# EtherWiz_Controller.net
KiCad netlist of a schematic drawn in Altium Designer
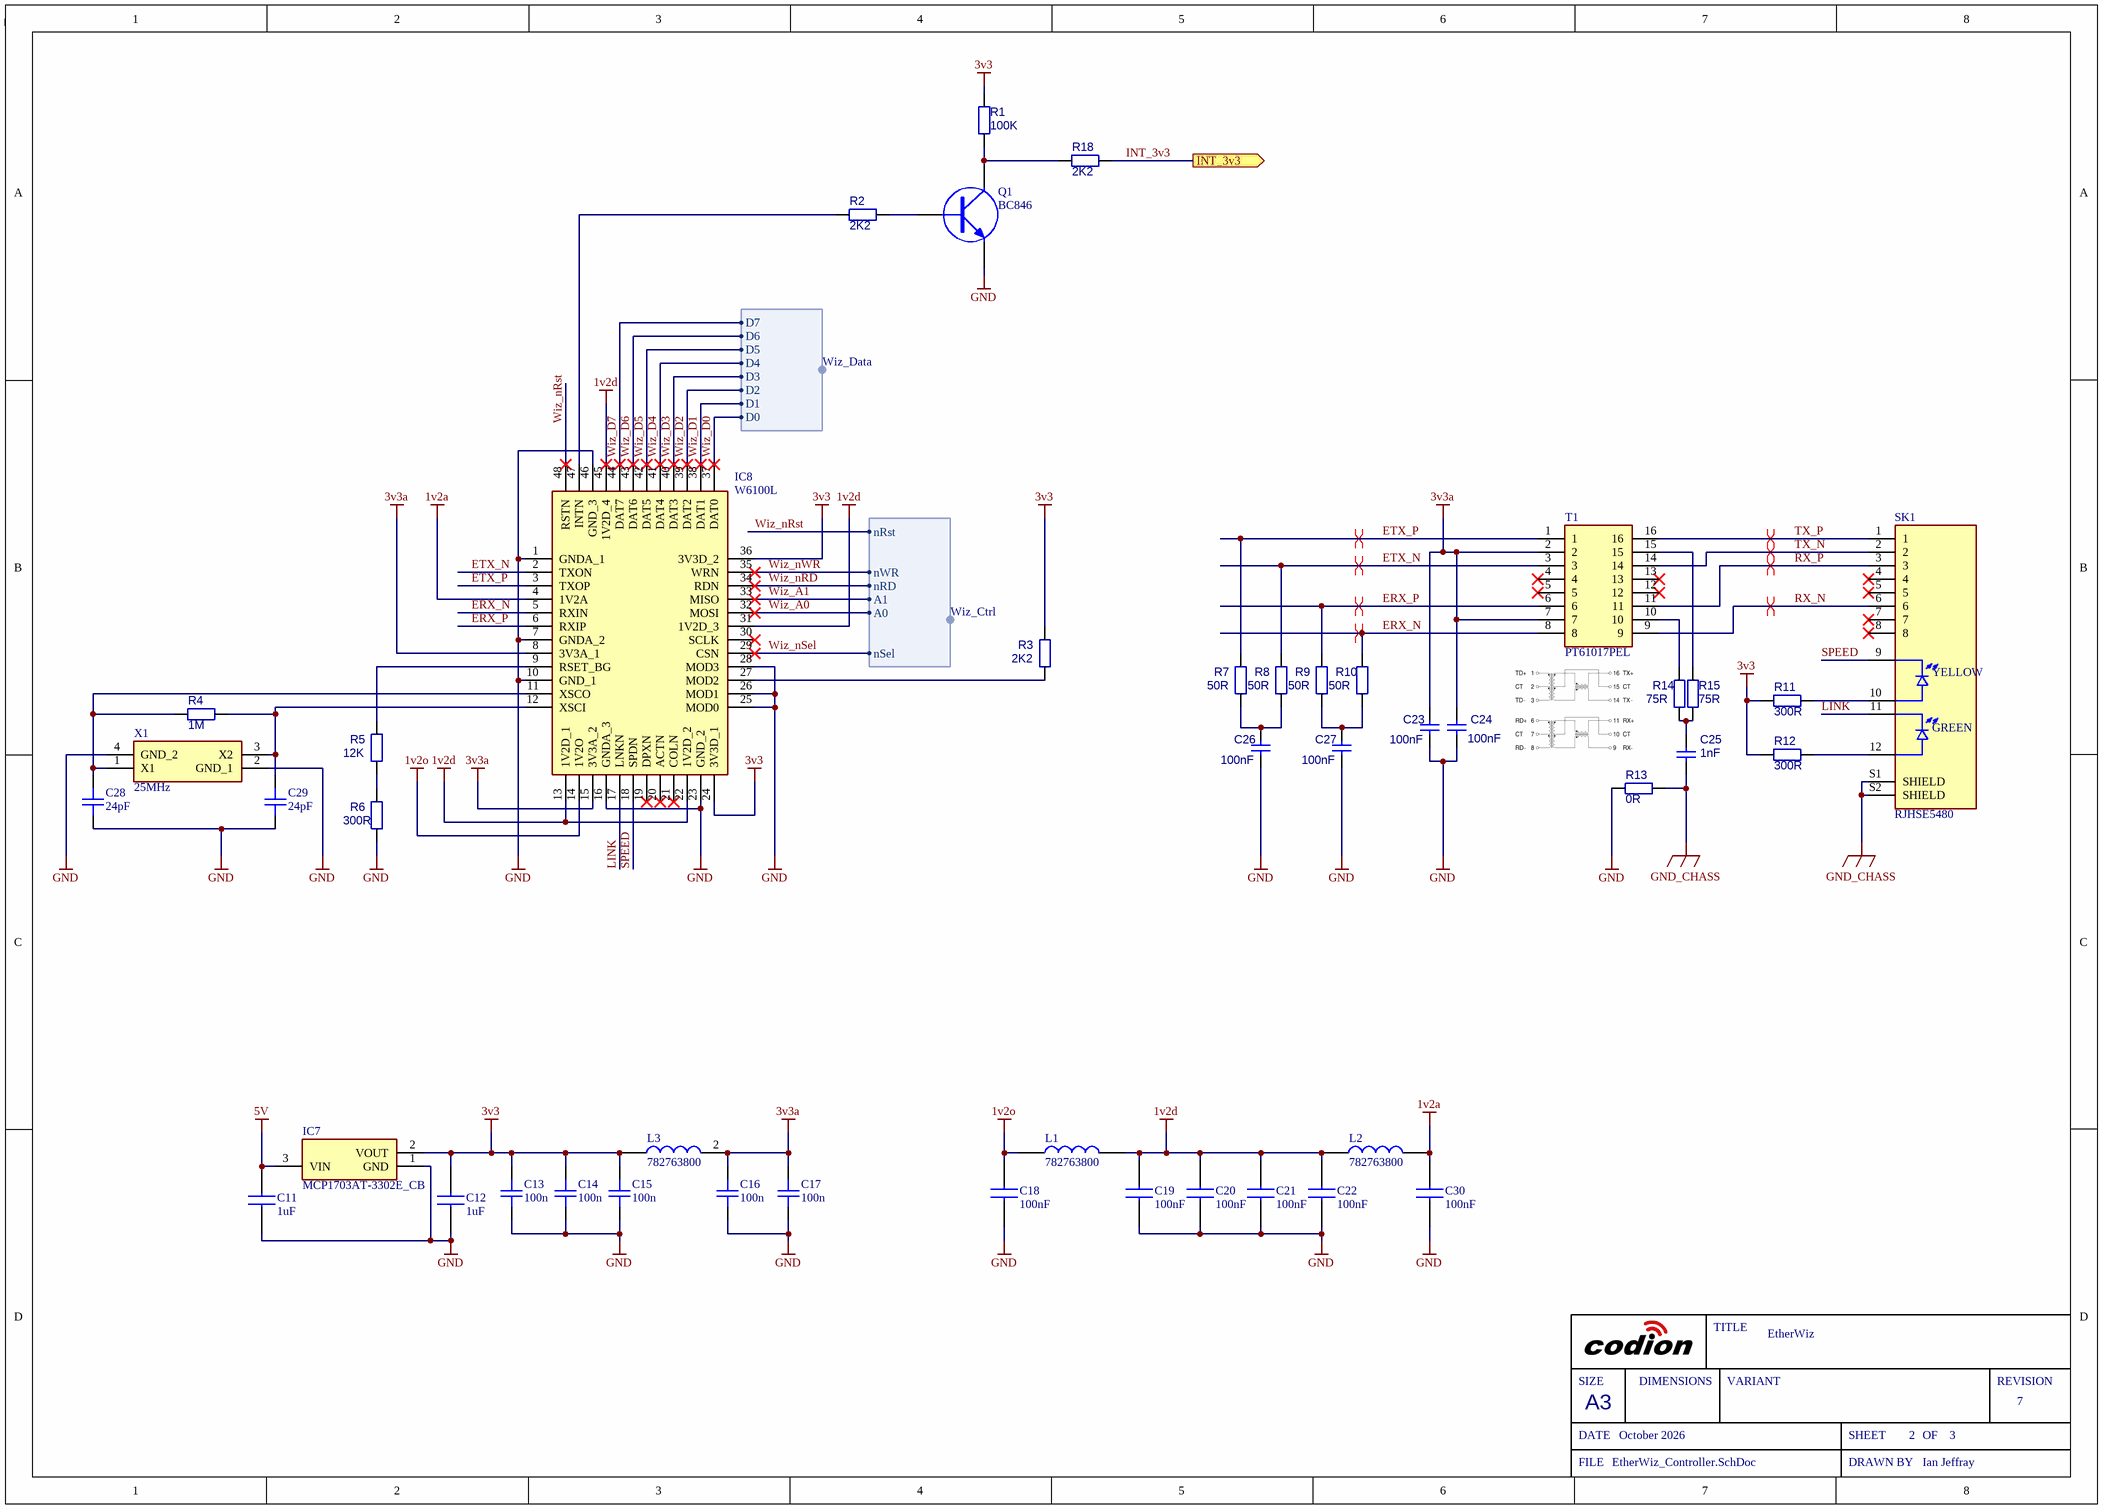
[diagram p0: EtherWiz_Controller.SchDoc]

(export (version "E")
  (design (tool "Eeschema 10.0.6"))
  (components
    (comp (ref "C11")
      (value "1uF")
      (footprint "SamacSys:CAPC1608X90N")
      (description "Capacitor")
      (fields
        (field (name "MANUFACTURER_PART_NUMBER") "CL10A105KP8NNNC")
        (field (name "MOUSER PART NUMBER") "187-CL10A105KP8NNNC")
      )
      (libsource (lib "*") (part "CL10A105KP8NNNC"))
    )
    (comp (ref "C12")
      (value "1uF")
      (footprint "SamacSys:CAPC1608X90N")
      (description "Capacitor")
      (fields
        (field (name "MANUFACTURER_PART_NUMBER") "CL10A105KP8NNNC")
        (field (name "MOUSER PART NUMBER") "187-CL10A105KP8NNNC")
      )
      (libsource (lib "*") (part "CL10A105KP8NNNC"))
    )
    (comp (ref "C13")
      (value "100n")
      (footprint "CAPC1608L")
      (description "CAP 100nF, 0603, 50V, X7R, 10%")
      (fields
        (field (name "DISTRIBUTOR1 PART NO") "CL10B104KB8NNNC")
        (field (name "DISTRIBUTOR2 PART NO") "311-1344-2-ND")
      )
      (libsource (lib "MCP1002_RevC") (part "CAP_100n_0603_50V_0"))
    )
    (comp (ref "C14")
      (value "100n")
      (footprint "CAPC1608L")
      (description "CAP 100nF, 0603, 50V, X7R, 10%")
      (fields
        (field (name "DISTRIBUTOR1 PART NO") "CL10B104KB8NNNC")
        (field (name "DISTRIBUTOR2 PART NO") "311-1344-2-ND")
      )
      (libsource (lib "MCP1002_RevC") (part "CAP_100n_0603_50V_0"))
    )
    (comp (ref "C15")
      (value "100n")
      (footprint "CAPC1608L")
      (description "CAP 100nF, 0603, 50V, X7R, 10%")
      (fields
        (field (name "DISTRIBUTOR1 PART NO") "CL10B104KB8NNNC")
        (field (name "DISTRIBUTOR2 PART NO") "311-1344-2-ND")
      )
      (libsource (lib "MCP1002_RevC") (part "CAP_100n_0603_50V_0"))
    )
    (comp (ref "C16")
      (value "100n")
      (footprint "CAPC1608L")
      (description "CAP 100nF, 0603, 50V, X7R, 10%")
      (fields
        (field (name "DISTRIBUTOR1 PART NO") "CL10B104KB8NNNC")
        (field (name "DISTRIBUTOR2 PART NO") "311-1344-2-ND")
      )
      (libsource (lib "MCP1002_RevC") (part "CAP_100n_0603_50V_0"))
    )
    (comp (ref "C17")
      (value "100n")
      (footprint "CAPC1608L")
      (description "CAP 100nF, 0603, 50V, X7R, 10%")
      (fields
        (field (name "DISTRIBUTOR1 PART NO") "CL10B104KB8NNNC")
        (field (name "DISTRIBUTOR2 PART NO") "311-1344-2-ND")
      )
      (libsource (lib "MCP1002_RevC") (part "CAP_100n_0603_50V_0"))
    )
    (comp (ref "C18")
      (value "100nF")
      (footprint "CAPC1608L")
      (description "Capacitor")
      (fields
        (field (name "MANUFACTURER_PART_NUMBER") "C2012X7R1H104K125AM")
        (field (name "MOUSER PART NUMBER") "810-C2012X7R1H104KT5")
      )
      (libsource (lib "Acorn") (part "100nF0805"))
    )
    (comp (ref "C19")
      (value "100nF")
      (footprint "CAPC1608L")
      (description "Capacitor")
      (fields
        (field (name "MANUFACTURER_PART_NUMBER") "C2012X7R1H104K125AM")
        (field (name "MOUSER PART NUMBER") "810-C2012X7R1H104KT5")
      )
      (libsource (lib "Acorn") (part "100nF0805"))
    )
    (comp (ref "C20")
      (value "100nF")
      (footprint "CAPC1608L")
      (description "Capacitor")
      (fields
        (field (name "MANUFACTURER_PART_NUMBER") "C2012X7R1H104K125AM")
        (field (name "MOUSER PART NUMBER") "810-C2012X7R1H104KT5")
      )
      (libsource (lib "Acorn") (part "100nF0805"))
    )
    (comp (ref "C21")
      (value "100nF")
      (footprint "CAPC1608L")
      (description "Capacitor")
      (fields
        (field (name "MANUFACTURER_PART_NUMBER") "C2012X7R1H104K125AM")
        (field (name "MOUSER PART NUMBER") "810-C2012X7R1H104KT5")
      )
      (libsource (lib "Acorn") (part "100nF0805"))
    )
    (comp (ref "C22")
      (value "100nF")
      (footprint "CAPC1608L")
      (description "Capacitor")
      (fields
        (field (name "MANUFACTURER_PART_NUMBER") "C2012X7R1H104K125AM")
        (field (name "MOUSER PART NUMBER") "810-C2012X7R1H104KT5")
      )
      (libsource (lib "Acorn") (part "100nF0805"))
    )
    (comp (ref "C23")
      (value "100nF")
      (footprint "CAPC1608L")
      (description "Cap ceramic X7R/X5R 100nF 10% 16V C0603")
      (fields (field (name "TOLERANCE") "0.1") (field (name "VOLTAGE") "16V"))
      (libsource (lib "Local_Altium_Lib") (part "Capacitor - non polarized"))
    )
    (comp (ref "C24")
      (value "100nF")
      (footprint "CAPC1608L")
      (description "Cap ceramic X7R/X5R 100nF 10% 16V C0603")
      (fields (field (name "TOLERANCE") "0.1") (field (name "VOLTAGE") "16V"))
      (libsource (lib "Local_Altium_Lib") (part "Capacitor - non polarized"))
    )
    (comp (ref "C25")
      (value "1nF")
      (footprint "CAPC1608L")
      (description "Cap ceramic X7R 1nF 10% 2kV C1206")
      (fields (field (name "TOLERANCE") "0.1") (field (name "VOLTAGE") "2000V"))
      (libsource (lib "Local_Altium_Lib") (part "Capacitor - non polarized"))
    )
    (comp (ref "C26")
      (value "100nF")
      (footprint "CAPC1608L")
      (description "Cap ceramic X7R/X5R 100nF 10% 16V C0603")
      (fields (field (name "TOLERANCE") "0.1") (field (name "VOLTAGE") "16V"))
      (libsource (lib "Local_Altium_Lib") (part "Capacitor - non polarized"))
    )
    (comp (ref "C27")
      (value "100nF")
      (footprint "CAPC1608L")
      (description "Cap ceramic X7R/X5R 100nF 10% 16V C0603")
      (fields (field (name "TOLERANCE") "0.1") (field (name "VOLTAGE") "16V"))
      (libsource (lib "Local_Altium_Lib") (part "Capacitor - non polarized"))
    )
    (comp (ref "C28")
      (value "24pF")
      (footprint "CAPC1608L")
      (description "CAP 10PF, 0603, 50V, NP0, 10%")
      (libsource (lib "MCP1010_RevA") (part "CAP_10P_0603_50V_0"))
    )
    (comp (ref "C29")
      (value "24pF")
      (footprint "CAPC1608L")
      (description "CAP 10PF, 0603, 50V, NP0, 10%")
      (libsource (lib "MCP1010_RevA") (part "CAP_10P_0603_50V_0"))
    )
    (comp (ref "C30")
      (value "100nF")
      (footprint "CAPC1608L")
      (description "Capacitor")
      (fields
        (field (name "MANUFACTURER_PART_NUMBER") "C2012X7R1H104K125AM")
        (field (name "MOUSER PART NUMBER") "810-C2012X7R1H104KT5")
      )
      (libsource (lib "Acorn") (part "100nF0805"))
    )
    (comp (ref "IC7")
      (value "MCP1703AT-3302E_CB")
      (footprint "SamacSys:SOT95P255X145-3N")
      (description "Integrated Circuit")
      (fields
        (field (name "MANUFACTURER_PART_NUMBER") "MCP1703AT-3302E/CB")
        (field (name "MOUSER PART NUMBER") "579-MCP1703AT3302ECB")
      )
      (libsource (lib "*") (part "MCP1703AT-3302E_CB"))
    )
    (comp (ref "IC8")
      (value "W6100L")
      (footprint "SamacSys:QFP50P900X900X160-48N")
      (description "Integrated Circuit")
      (fields (field (name "MOUSER PART NUMBER") "950-W6100L"))
      (libsource (lib "*") (part "W6100L"))
    )
    (comp (ref "L1")
      (value "782763800")
      (footprint "SamacSys:INDC3216X130N")
      (description "Inductor")
      (fields (field (name "MOUSER PART NUMBER") "710-782763800"))
      (libsource (lib "*") (part "74279215"))
    )
    (comp (ref "L2")
      (value "782763800")
      (footprint "SamacSys:INDC3216X130N")
      (description "Inductor")
      (fields (field (name "MOUSER PART NUMBER") "710-782763800"))
      (libsource (lib "*") (part "74279215"))
    )
    (comp (ref "L3")
      (value "782763800")
      (footprint "SamacSys:INDC3216X130N")
      (description "Inductor")
      (fields (field (name "MOUSER PART NUMBER") "710-782763800"))
      (libsource (lib "") (part "74279215_1"))
    )
    (comp (ref "Q1")
      (value "BC846")
      (footprint "SOT-23")
      (description "Transistor NPN, 65V, 100mA, TO-236AB/SOT23")
      (libsource (lib "MCP1002_RevC") (part "TRANS_NPN_BC846_0"))
    )
    (comp (ref "R1")
      (value "100K")
      (footprint "RESC1608X50N")
      (description "Resistor 100K 1%  0603")
      (libsource (lib "Local_Altium_Lib") (part "Resistor - fixed"))
    )
    (comp (ref "R2")
      (value "2K2")
      (footprint "RESC1608X50N")
      (description "Resistor 2K2 1%  0603")
      (fields (field (name "TOLERANCE") "0.01") (field (name "POWER") "63mW"))
      (libsource (lib "") (part "Resistor - fixed_2"))
    )
    (comp (ref "R3")
      (value "2K2")
      (footprint "RESC1608X50N")
      (description "Resistor 2K2 1%  0603")
      (fields (field (name "TOLERANCE") "0.01") (field (name "POWER") "63mW"))
      (libsource (lib "Local_Altium_Lib") (part "Resistor - fixed"))
    )
    (comp (ref "R4")
      (value "1M")
      (footprint "RESC1608X50N")
      (description "Resistor 1M 1%  0603")
      (fields (field (name "TOLERANCE") "0.01") (field (name "POWER") "63mW"))
      (libsource (lib "") (part "Resistor - fixed_1"))
    )
    (comp (ref "R5")
      (value "12K")
      (footprint "RESC1608X50N")
      (description "Resistor 12K 1%  0603")
      (fields (field (name "TOLERANCE") "0.01") (field (name "POWER") "63mW"))
      (libsource (lib "Local_Altium_Lib") (part "Resistor - fixed"))
    )
    (comp (ref "R6")
      (value "300R")
      (footprint "RESC1608X50N")
      (description "Resistor 300R 1%  0603")
      (fields (field (name "TOLERANCE") "0.01") (field (name "POWER") "63mW"))
      (libsource (lib "Local_Altium_Lib") (part "Resistor - fixed"))
    )
    (comp (ref "R7")
      (value "50R")
      (footprint "RESC1608X50N")
      (description "Resistor 50R 1%  0603")
      (fields (field (name "TOLERANCE") "0.01") (field (name "POWER") "63mW"))
      (libsource (lib "Local_Altium_Lib") (part "Resistor - fixed"))
    )
    (comp (ref "R8")
      (value "50R")
      (footprint "RESC1608X50N")
      (description "Resistor 50R 1%  0603")
      (fields (field (name "TOLERANCE") "0.01") (field (name "POWER") "63mW"))
      (libsource (lib "Local_Altium_Lib") (part "Resistor - fixed"))
    )
    (comp (ref "R9")
      (value "50R")
      (footprint "RESC1608X50N")
      (description "Resistor 50R 1%  0603")
      (fields (field (name "TOLERANCE") "0.01") (field (name "POWER") "63mW"))
      (libsource (lib "Local_Altium_Lib") (part "Resistor - fixed"))
    )
    (comp (ref "R10")
      (value "50R")
      (footprint "RESC1608X50N")
      (description "Resistor 50R 1%  0603")
      (fields (field (name "TOLERANCE") "0.01") (field (name "POWER") "63mW"))
      (libsource (lib "Local_Altium_Lib") (part "Resistor - fixed"))
    )
    (comp (ref "R11")
      (value "300R")
      (footprint "RESC1608X50N")
      (description "Resistor 300R 1%  0603")
      (libsource (lib "") (part "Resistor - fixed_1"))
    )
    (comp (ref "R12")
      (value "300R")
      (footprint "RESC1608X50N")
      (description "Resistor 300R 1%  0603")
      (libsource (lib "") (part "Resistor - fixed_1"))
    )
    (comp (ref "R13")
      (value "0R")
      (footprint "RESC1608L")
      (description "Resistor 0R0 1A Max 0603")
      (fields (field (name "MANUFACTURER") "Vishay") (field (name "MANUPART") "CRCW06030000Z0EA"))
      (libsource (lib "") (part "Resistor - fixed_2"))
    )
    (comp (ref "R14")
      (value "75R")
      (footprint "RESC1608L")
      (description "Resistor 75R 1%  0603")
      (fields (field (name "TOLERANCE") "0.01") (field (name "POWER") "63mW"))
      (libsource (lib "Local_Altium_Lib") (part "Resistor - fixed"))
    )
    (comp (ref "R15")
      (value "75R")
      (footprint "RESC1608L")
      (description "Resistor 75R 1%  0603")
      (fields (field (name "TOLERANCE") "0.01") (field (name "POWER") "63mW"))
      (libsource (lib "Local_Altium_Lib") (part "Resistor - fixed"))
    )
    (comp (ref "R18")
      (value "2K2")
      (footprint "RESC1608X50N")
      (description "Resistor 2K2 1%  0603")
      (fields (field (name "TOLERANCE") "0.01") (field (name "POWER") "63mW"))
      (libsource (lib "") (part "Resistor - fixed_2"))
    )
    (comp (ref "SK1")
      (value "RJHSE5480")
      (footprint "AMPHENOL_RJHSE5480")
      (description "Ethernet socket - through hole")
      (fields (field (name "MANUPART") "RJHSE-5480") (field (name "MANUFACTURER") "Amphenol"))
      (libsource (lib "RJHSE5480") (part "RJHSE5480"))
    )
    (comp (ref "T1")
      (value "PT61017PEL")
      (footprint "SamacSys:PT61017PEL")
      (description "Transformer")
      (fields (field (name "MANUFACTURER") "Bourns") (field (name "DISTI PART NUMBER") "652-PT61017PEL"))
      (libsource (lib "*") (part "PT61017PEL"))
    )
    (comp (ref "X1")
      (value "25MHz")
      (footprint "SamacSys:ABM810000MHZ12D2W")
      (description "Crystal or Oscillator")
      (fields
        (field (name "MANUFACTURER_PART_NUMBER") "ABM8-25.000MHZ-D2X-T")
        (field (name "MOUSER PART NUMBER") "815-ABM825MHZD2XT")
      )
      (libsource (lib "*") (part "ABM8-25.000MHZ-D2X-T"))
    )
  )
  (nets
    (net (code "1") (name "/ERX_N") (class "Default")
      (node (ref "IC8") (pin "5") (pinfunction "RXIN_5") (pintype "passive"))
      (node (ref "R10") (pin "2") (pinfunction "2_2") (pintype "passive"))
      (node (ref "T1") (pin "8") (pinfunction "8_8") (pintype "passive"))
    )
    (net (code "2") (name "/ERX_P") (class "Default")
      (node (ref "IC8") (pin "6") (pinfunction "RXIP_6") (pintype "passive"))
      (node (ref "R9") (pin "2") (pinfunction "2_2") (pintype "passive"))
      (node (ref "T1") (pin "6") (pinfunction "6_6") (pintype "passive"))
    )
    (net (code "3") (name "/ETX_N") (class "Default")
      (node (ref "IC8") (pin "2") (pinfunction "TXON_2") (pintype "passive"))
      (node (ref "R8") (pin "2") (pinfunction "2_2") (pintype "passive"))
      (node (ref "T1") (pin "3") (pinfunction "3_3") (pintype "passive"))
    )
    (net (code "4") (name "/ETX_P") (class "Default")
      (node (ref "IC8") (pin "3") (pinfunction "TXOP_3") (pintype "passive"))
      (node (ref "R7") (pin "2") (pinfunction "2_2") (pintype "passive"))
      (node (ref "T1") (pin "1") (pinfunction "1_1") (pintype "passive"))
    )
    (net (code "5") (name "/INT_3v3") (class "Default")
      (node (ref "R18") (pin "2") (pinfunction "2_2") (pintype "passive"))
    )
    (net (code "6") (name "/LINK") (class "Default")
      (node (ref "IC8") (pin "17") (pinfunction "LNKN_17") (pintype "passive"))
      (node (ref "SK1") (pin "11") (pinfunction "11_11") (pintype "passive"))
    )
    (net (code "7") (name "/RX_N") (class "Default")
      (node (ref "SK1") (pin "6") (pinfunction "6_6") (pintype "passive"))
      (node (ref "T1") (pin "9") (pinfunction "9_9") (pintype "passive"))
    )
    (net (code "8") (name "/RX_P") (class "Default")
      (node (ref "SK1") (pin "3") (pinfunction "3_3") (pintype "passive"))
      (node (ref "T1") (pin "11") (pinfunction "11_11") (pintype "passive"))
    )
    (net (code "9") (name "/SPEED") (class "Default")
      (node (ref "IC8") (pin "18") (pinfunction "SPDN_18") (pintype "passive"))
      (node (ref "SK1") (pin "9") (pinfunction "9_9") (pintype "passive"))
    )
    (net (code "10") (name "/TX_N") (class "Default")
      (node (ref "SK1") (pin "2") (pinfunction "2_2") (pintype "passive"))
      (node (ref "T1") (pin "14") (pinfunction "14_14") (pintype "passive"))
    )
    (net (code "11") (name "/TX_P") (class "Default")
      (node (ref "SK1") (pin "1") (pinfunction "1_1") (pintype "passive"))
      (node (ref "T1") (pin "16") (pinfunction "16_16") (pintype "passive"))
    )
    (net (code "12") (name "/Wiz_A0") (class "Default")
      (node (ref "IC8") (pin "32") (pinfunction "MOSI_32") (pintype "passive+no_connect"))
    )
    (net (code "13") (name "/Wiz_A1") (class "Default")
      (node (ref "IC8") (pin "33") (pinfunction "MISO_33") (pintype "passive+no_connect"))
    )
    (net (code "14") (name "/Wiz_D0") (class "Default")
      (node (ref "IC8") (pin "37") (pinfunction "DAT0_37") (pintype "passive+no_connect"))
    )
    (net (code "15") (name "/Wiz_D1") (class "Default")
      (node (ref "IC8") (pin "38") (pinfunction "DAT1_38") (pintype "passive+no_connect"))
    )
    (net (code "16") (name "/Wiz_D2") (class "Default")
      (node (ref "IC8") (pin "39") (pinfunction "DAT2_39") (pintype "passive+no_connect"))
    )
    (net (code "17") (name "/Wiz_D3") (class "Default")
      (node (ref "IC8") (pin "40") (pinfunction "DAT3_40") (pintype "passive+no_connect"))
    )
    (net (code "18") (name "/Wiz_D4") (class "Default")
      (node (ref "IC8") (pin "41") (pinfunction "DAT4_41") (pintype "passive+no_connect"))
    )
    (net (code "19") (name "/Wiz_D5") (class "Default")
      (node (ref "IC8") (pin "42") (pinfunction "DAT5_42") (pintype "passive+no_connect"))
    )
    (net (code "20") (name "/Wiz_D6") (class "Default")
      (node (ref "IC8") (pin "43") (pinfunction "DAT6_43") (pintype "passive+no_connect"))
    )
    (net (code "21") (name "/Wiz_D7") (class "Default")
      (node (ref "IC8") (pin "44") (pinfunction "DAT7_44") (pintype "passive+no_connect"))
    )
    (net (code "22") (name "/Wiz_nRD") (class "Default")
      (node (ref "IC8") (pin "34") (pinfunction "RDN_34") (pintype "passive+no_connect"))
    )
    (net (code "23") (name "/Wiz_nRst") (class "Default")
      (node (ref "IC8") (pin "48") (pinfunction "RSTN_48") (pintype "passive"))
    )
    (net (code "24") (name "/Wiz_nSel") (class "Default")
      (node (ref "IC8") (pin "29") (pinfunction "CSN_29") (pintype "passive+no_connect"))
    )
    (net (code "25") (name "/Wiz_nWR") (class "Default")
      (node (ref "IC8") (pin "35") (pinfunction "WRN_35") (pintype "passive+no_connect"))
    )
    (net (code "26") (name "1v2a") (class "Default")
      (node (ref "C30") (pin "2") (pinfunction "2_2") (pintype "passive"))
      (node (ref "IC8") (pin "4") (pinfunction "1V2A_4") (pintype "passive"))
      (node (ref "L2") (pin "2") (pinfunction "2_2") (pintype "passive"))
    )
    (net (code "27") (name "1v2d") (class "Default")
      (node (ref "C19") (pin "2") (pinfunction "2_2") (pintype "passive"))
      (node (ref "C20") (pin "2") (pinfunction "2_2") (pintype "passive"))
      (node (ref "C21") (pin "2") (pinfunction "2_2") (pintype "passive"))
      (node (ref "C22") (pin "2") (pinfunction "2_2") (pintype "passive"))
      (node (ref "IC8") (pin "13") (pinfunction "1V2D_1_13") (pintype "passive"))
      (node (ref "IC8") (pin "22") (pinfunction "1V2D_2_22") (pintype "passive"))
      (node (ref "IC8") (pin "31") (pinfunction "1V2D_3_31") (pintype "passive"))
      (node (ref "IC8") (pin "45") (pinfunction "1V2D_4_45") (pintype "passive"))
      (node (ref "L1") (pin "2") (pinfunction "2_2") (pintype "passive"))
      (node (ref "L2") (pin "1") (pinfunction "1_1") (pintype "passive"))
    )
    (net (code "28") (name "1v2o") (class "Default")
      (node (ref "C18") (pin "2") (pinfunction "2_2") (pintype "passive"))
      (node (ref "IC8") (pin "14") (pinfunction "1V2O_14") (pintype "passive"))
      (node (ref "L1") (pin "1") (pinfunction "1_1") (pintype "passive"))
    )
    (net (code "29") (name "3v3") (class "Default")
      (node (ref "C12") (pin "2") (pinfunction "2_2") (pintype "passive"))
      (node (ref "C13") (pin "2") (pintype "passive"))
      (node (ref "C14") (pin "2") (pintype "passive"))
      (node (ref "C15") (pin "2") (pintype "passive"))
      (node (ref "IC7") (pin "2") (pinfunction "VOUT_2") (pintype "passive"))
      (node (ref "IC8") (pin "24") (pinfunction "3V3D_1_24") (pintype "passive"))
      (node (ref "IC8") (pin "36") (pinfunction "3V3D_2_36") (pintype "passive"))
      (node (ref "L3") (pin "1") (pinfunction "1_1") (pintype "passive"))
      (node (ref "R1") (pin "2") (pinfunction "2_2") (pintype "passive"))
      (node (ref "R11") (pin "2") (pinfunction "2_2") (pintype "passive"))
      (node (ref "R12") (pin "2") (pinfunction "2_2") (pintype "passive"))
      (node (ref "R3") (pin "2") (pinfunction "2_2") (pintype "passive"))
    )
    (net (code "30") (name "3v3a") (class "Default")
      (node (ref "C16") (pin "2") (pintype "passive"))
      (node (ref "C17") (pin "2") (pintype "passive"))
      (node (ref "C23") (pin "2") (pinfunction "2_2") (pintype "passive"))
      (node (ref "C24") (pin "2") (pinfunction "2_2") (pintype "passive"))
      (node (ref "IC8") (pin "15") (pinfunction "3V3A_2_15") (pintype "passive"))
      (node (ref "IC8") (pin "8") (pinfunction "3V3A_1_8") (pintype "passive"))
      (node (ref "L3") (pin "2") (pinfunction "2_2") (pintype "passive"))
      (node (ref "T1") (pin "2") (pinfunction "2_2") (pintype "passive"))
      (node (ref "T1") (pin "7") (pinfunction "7_7") (pintype "passive"))
    )
    (net (code "31") (name "5V") (class "Default")
      (node (ref "C11") (pin "2") (pinfunction "2_2") (pintype "passive"))
      (node (ref "IC7") (pin "3") (pinfunction "VIN_3") (pintype "passive"))
    )
    (net (code "32") (name "GND") (class "Default")
      (node (ref "C11") (pin "1") (pinfunction "1_1") (pintype "passive"))
      (node (ref "C12") (pin "1") (pinfunction "1_1") (pintype "passive"))
      (node (ref "C13") (pin "1") (pintype "passive"))
      (node (ref "C14") (pin "1") (pintype "passive"))
      (node (ref "C15") (pin "1") (pintype "passive"))
      (node (ref "C16") (pin "1") (pintype "passive"))
      (node (ref "C17") (pin "1") (pintype "passive"))
      (node (ref "C18") (pin "1") (pinfunction "1_1") (pintype "passive"))
      (node (ref "C19") (pin "1") (pinfunction "1_1") (pintype "passive"))
      (node (ref "C20") (pin "1") (pinfunction "1_1") (pintype "passive"))
      (node (ref "C21") (pin "1") (pinfunction "1_1") (pintype "passive"))
      (node (ref "C22") (pin "1") (pinfunction "1_1") (pintype "passive"))
      (node (ref "C23") (pin "1") (pinfunction "1_1") (pintype "passive"))
      (node (ref "C24") (pin "1") (pinfunction "1_1") (pintype "passive"))
      (node (ref "C26") (pin "1") (pinfunction "1_1") (pintype "passive"))
      (node (ref "C27") (pin "1") (pinfunction "1_1") (pintype "passive"))
      (node (ref "C28") (pin "1") (pintype "passive"))
      (node (ref "C29") (pin "1") (pintype "passive"))
      (node (ref "C30") (pin "1") (pinfunction "1_1") (pintype "passive"))
      (node (ref "IC7") (pin "1") (pinfunction "GND_1") (pintype "passive"))
      (node (ref "IC8") (pin "1") (pinfunction "GNDA_1_1") (pintype "passive"))
      (node (ref "IC8") (pin "10") (pinfunction "GND_1_10") (pintype "passive"))
      (node (ref "IC8") (pin "16") (pinfunction "GNDA_3_16") (pintype "passive"))
      (node (ref "IC8") (pin "23") (pinfunction "GND_2_23") (pintype "passive"))
      (node (ref "IC8") (pin "25") (pinfunction "MOD0_25") (pintype "passive"))
      (node (ref "IC8") (pin "26") (pinfunction "MOD1_26") (pintype "passive"))
      (node (ref "IC8") (pin "28") (pinfunction "MOD3_28") (pintype "passive"))
      (node (ref "IC8") (pin "46") (pinfunction "GND_3_46") (pintype "passive"))
      (node (ref "IC8") (pin "7") (pinfunction "GNDA_2_7") (pintype "passive"))
      (node (ref "Q1") (pin "2") (pinfunction "E_2") (pintype "passive"))
      (node (ref "R13") (pin "1") (pinfunction "1_1") (pintype "passive"))
      (node (ref "R6") (pin "1") (pinfunction "1_1") (pintype "passive"))
      (node (ref "X1") (pin "2") (pinfunction "GND_1_2") (pintype "passive"))
      (node (ref "X1") (pin "4") (pinfunction "GND_2_4") (pintype "passive"))
    )
    (net (code "33") (name "GND_CHASS") (class "Default")
      (node (ref "C25") (pin "1") (pinfunction "1_1") (pintype "passive"))
      (node (ref "R13") (pin "2") (pinfunction "2_2") (pintype "passive"))
      (node (ref "SK1") (pin "S1") (pinfunction "SHIELD_S1") (pintype "passive"))
      (node (ref "SK1") (pin "S2") (pinfunction "SHIELD_S2") (pintype "passive"))
    )
    (net (code "34") (name "Net-(C25-Pad2)") (class "Default")
      (node (ref "C25") (pin "2") (pinfunction "2_2") (pintype "passive"))
      (node (ref "R14") (pin "1") (pinfunction "1_1") (pintype "passive"))
      (node (ref "R15") (pin "1") (pinfunction "1_1") (pintype "passive"))
    )
    (net (code "35") (name "Net-(C26-Pad2)") (class "Default")
      (node (ref "C26") (pin "2") (pinfunction "2_2") (pintype "passive"))
      (node (ref "R7") (pin "1") (pinfunction "1_1") (pintype "passive"))
      (node (ref "R8") (pin "1") (pinfunction "1_1") (pintype "passive"))
    )
    (net (code "36") (name "Net-(C27-Pad2)") (class "Default")
      (node (ref "C27") (pin "2") (pinfunction "2_2") (pintype "passive"))
      (node (ref "R10") (pin "1") (pinfunction "1_1") (pintype "passive"))
      (node (ref "R9") (pin "1") (pinfunction "1_1") (pintype "passive"))
    )
    (net (code "37") (name "Net-(IC8-INTN)") (class "Default")
      (node (ref "IC8") (pin "47") (pinfunction "INTN_47") (pintype "passive"))
      (node (ref "R2") (pin "1") (pinfunction "1_1") (pintype "passive"))
    )
    (net (code "38") (name "Net-(IC8-MOD2)") (class "Default")
      (node (ref "IC8") (pin "27") (pinfunction "MOD2_27") (pintype "passive"))
      (node (ref "R3") (pin "1") (pinfunction "1_1") (pintype "passive"))
    )
    (net (code "39") (name "Net-(IC8-RSET_BG)") (class "Default")
      (node (ref "IC8") (pin "9") (pinfunction "RSET_BG_9") (pintype "passive"))
      (node (ref "R5") (pin "2") (pinfunction "2_2") (pintype "passive"))
    )
    (net (code "40") (name "Net-(IC8-XSCI)") (class "Default")
      (node (ref "C29") (pin "2") (pintype "passive"))
      (node (ref "IC8") (pin "12") (pinfunction "XSCI_12") (pintype "passive"))
      (node (ref "R4") (pin "1") (pinfunction "1_1") (pintype "passive"))
      (node (ref "X1") (pin "3") (pinfunction "X2_3") (pintype "passive"))
    )
    (net (code "41") (name "Net-(IC8-XSCO)") (class "Default")
      (node (ref "C28") (pin "2") (pintype "passive"))
      (node (ref "IC8") (pin "11") (pinfunction "XSCO_11") (pintype "passive"))
      (node (ref "R4") (pin "2") (pinfunction "2_2") (pintype "passive"))
      (node (ref "X1") (pin "1") (pinfunction "X1_1") (pintype "passive"))
    )
    (net (code "42") (name "Net-(Q1-B)") (class "Default")
      (node (ref "Q1") (pin "1") (pinfunction "B_1") (pintype "passive"))
      (node (ref "R2") (pin "2") (pinfunction "2_2") (pintype "passive"))
    )
    (net (code "43") (name "Net-(Q1-C)") (class "Default")
      (node (ref "Q1") (pin "3") (pinfunction "C_3") (pintype "passive"))
      (node (ref "R1") (pin "1") (pinfunction "1_1") (pintype "passive"))
      (node (ref "R18") (pin "1") (pinfunction "1_1") (pintype "passive"))
    )
    (net (code "44") (name "Net-(R5-Pad1)") (class "Default")
      (node (ref "R5") (pin "1") (pinfunction "1_1") (pintype "passive"))
      (node (ref "R6") (pin "2") (pinfunction "2_2") (pintype "passive"))
    )
    (net (code "45") (name "Net-(R11-Pad1)") (class "Default")
      (node (ref "R11") (pin "1") (pinfunction "1_1") (pintype "passive"))
      (node (ref "SK1") (pin "10") (pinfunction "10_10") (pintype "passive"))
    )
    (net (code "46") (name "Net-(R12-Pad1)") (class "Default")
      (node (ref "R12") (pin "1") (pinfunction "1_1") (pintype "passive"))
      (node (ref "SK1") (pin "12") (pinfunction "12_12") (pintype "passive"))
    )
    (net (code "47") (name "Net-(R14-Pad2)") (class "Default")
      (node (ref "R14") (pin "2") (pinfunction "2_2") (pintype "passive"))
      (node (ref "T1") (pin "10") (pinfunction "10_10") (pintype "passive"))
    )
    (net (code "48") (name "Net-(R15-Pad2)") (class "Default")
      (node (ref "R15") (pin "2") (pinfunction "2_2") (pintype "passive"))
      (node (ref "T1") (pin "15") (pinfunction "15_15") (pintype "passive"))
    )
    (net (code "49") (name "unconnected-(IC8-ACTN-Pad20)") (class "Default")
      (node (ref "IC8") (pin "20") (pinfunction "ACTN_20") (pintype "passive+no_connect"))
    )
    (net (code "50") (name "unconnected-(IC8-COLN-Pad21)") (class "Default")
      (node (ref "IC8") (pin "21") (pinfunction "COLN_21") (pintype "passive+no_connect"))
    )
    (net (code "51") (name "unconnected-(IC8-DPXN-Pad19)") (class "Default")
      (node (ref "IC8") (pin "19") (pinfunction "DPXN_19") (pintype "passive+no_connect"))
    )
    (net (code "52") (name "unconnected-(IC8-SCLK-Pad30)") (class "Default")
      (node (ref "IC8") (pin "30") (pinfunction "SCLK_30") (pintype "passive+no_connect"))
    )
    (net (code "53") (name "unconnected-(SK1-Pad4)") (class "Default")
      (node (ref "SK1") (pin "4") (pinfunction "4_4") (pintype "passive+no_connect"))
    )
    (net (code "54") (name "unconnected-(SK1-Pad5)") (class "Default")
      (node (ref "SK1") (pin "5") (pinfunction "5_5") (pintype "passive+no_connect"))
    )
    (net (code "55") (name "unconnected-(SK1-Pad7)") (class "Default")
      (node (ref "SK1") (pin "7") (pinfunction "7_7") (pintype "passive+no_connect"))
    )
    (net (code "56") (name "unconnected-(SK1-Pad8)") (class "Default")
      (node (ref "SK1") (pin "8") (pinfunction "8_8") (pintype "passive+no_connect"))
    )
    (net (code "57") (name "unconnected-(T1-Pad4)") (class "Default")
      (node (ref "T1") (pin "4") (pinfunction "4_4") (pintype "passive+no_connect"))
    )
    (net (code "58") (name "unconnected-(T1-Pad5)") (class "Default")
      (node (ref "T1") (pin "5") (pinfunction "5_5") (pintype "passive+no_connect"))
    )
    (net (code "59") (name "unconnected-(T1-Pad12)") (class "Default")
      (node (ref "T1") (pin "12") (pinfunction "12_12") (pintype "passive+no_connect"))
    )
    (net (code "60") (name "unconnected-(T1-Pad13)") (class "Default")
      (node (ref "T1") (pin "13") (pinfunction "13_13") (pintype "passive+no_connect"))
    )
  )
)
